# FPGA_POWER.net
KiCad netlist of a schematic drawn in Altium Designer
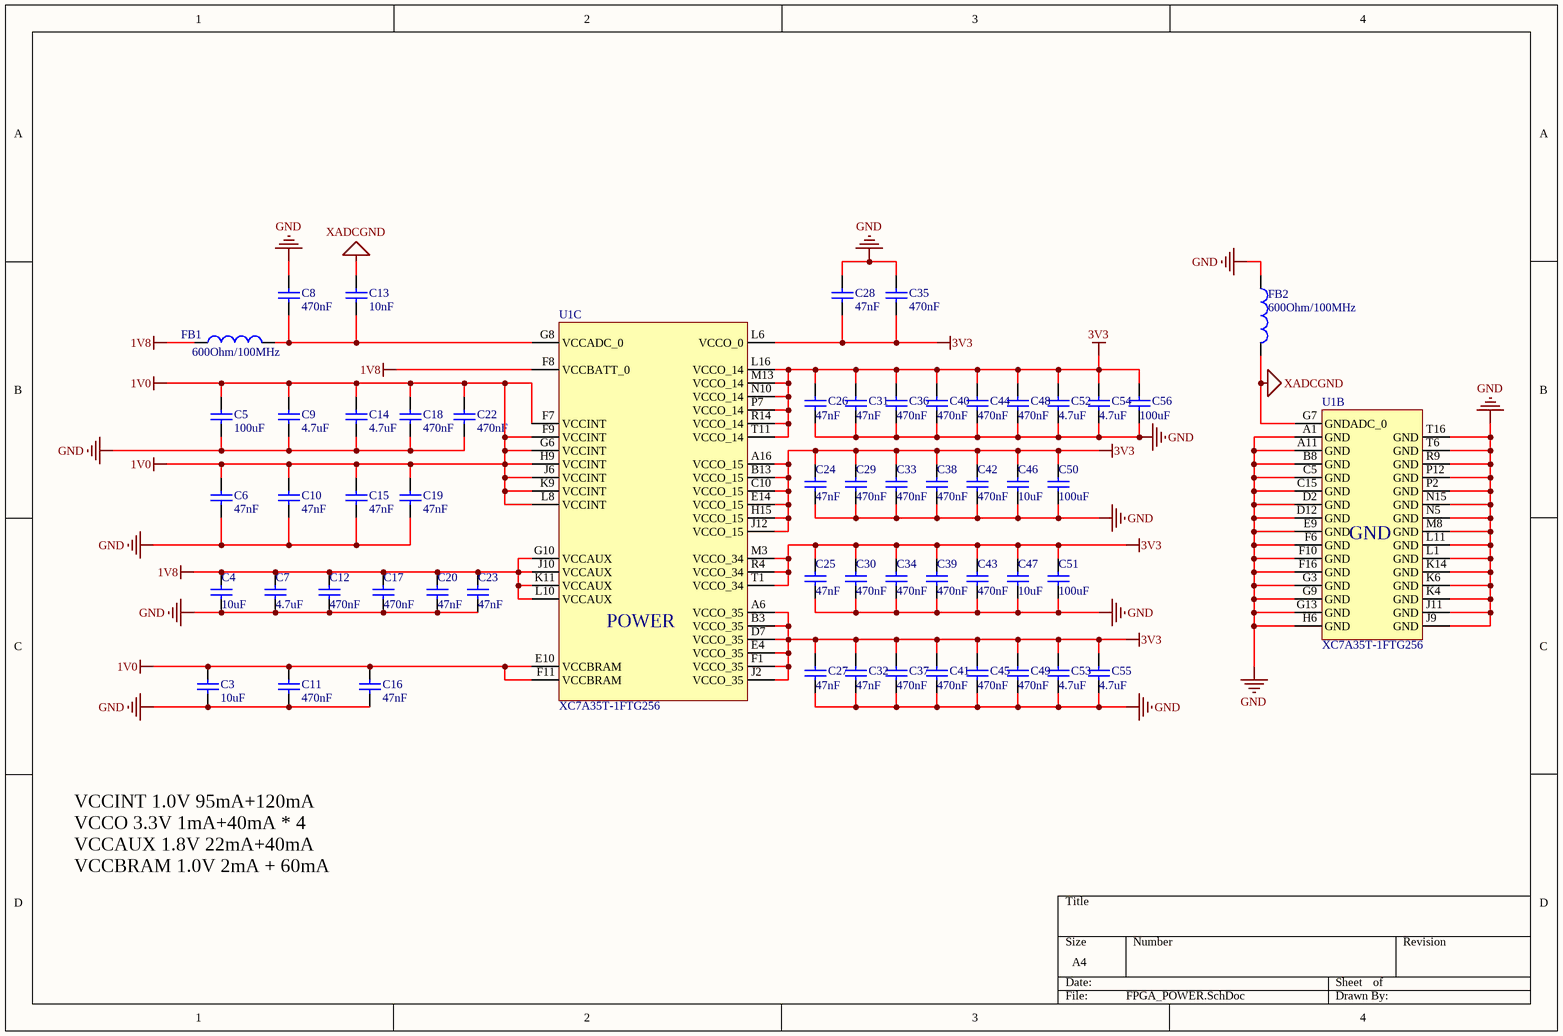
[diagram p0: FPGA_POWER.SchDoc]

(export (version "E")
  (design (tool "Eeschema 10.0.6"))
  (components
    (comp (ref "C3")
      (value "10uF")
      (footprint "0402")
      (description "贴片电容")
      (fields (field (name "Comment") "Cap") (field (name "PUBLISHER") "Altium Limited"))
      (libsource (lib "Sparks") (part "Cap"))
    )
    (comp (ref "C4")
      (value "10uF")
      (footprint "0402")
      (description "贴片电容")
      (fields (field (name "Comment") "Cap") (field (name "PUBLISHER") "Altium Limited"))
      (libsource (lib "Sparks") (part "Cap"))
    )
    (comp (ref "C5")
      (value "100uF")
      (footprint "2512")
      (description "贴片电容")
      (fields (field (name "Comment") "Cap") (field (name "PUBLISHER") "Altium Limited"))
      (libsource (lib "Sparks") (part "Cap"))
    )
    (comp (ref "C6")
      (value "47nF")
      (footprint "0402")
      (description "贴片电容")
      (fields (field (name "Comment") "Cap") (field (name "PUBLISHER") "Altium Limited"))
      (libsource (lib "Sparks") (part "Cap"))
    )
    (comp (ref "C7")
      (value "4.7uF")
      (footprint "0402")
      (description "贴片电容")
      (fields (field (name "Comment") "Cap") (field (name "PUBLISHER") "Altium Limited"))
      (libsource (lib "Sparks") (part "Cap"))
    )
    (comp (ref "C8")
      (value "470nF")
      (footprint "0402")
      (description "贴片电容")
      (fields (field (name "Comment") "Cap") (field (name "PUBLISHER") "Altium Limited"))
      (libsource (lib "Sparks") (part "Cap"))
    )
    (comp (ref "C9")
      (value "4.7uF")
      (footprint "0402")
      (description "贴片电容")
      (fields (field (name "Comment") "Cap") (field (name "PUBLISHER") "Altium Limited"))
      (libsource (lib "Sparks") (part "Cap"))
    )
    (comp (ref "C10")
      (value "47nF")
      (footprint "0402")
      (description "贴片电容")
      (fields (field (name "Comment") "Cap") (field (name "PUBLISHER") "Altium Limited"))
      (libsource (lib "Sparks") (part "Cap"))
    )
    (comp (ref "C11")
      (value "470nF")
      (footprint "0402")
      (description "贴片电容")
      (fields (field (name "Comment") "Cap") (field (name "PUBLISHER") "Altium Limited"))
      (libsource (lib "Sparks") (part "Cap"))
    )
    (comp (ref "C12")
      (value "470nF")
      (footprint "0402")
      (description "贴片电容")
      (fields (field (name "Comment") "Cap") (field (name "PUBLISHER") "Altium Limited"))
      (libsource (lib "Sparks") (part "Cap"))
    )
    (comp (ref "C13")
      (value "10nF")
      (footprint "0402")
      (description "贴片电容")
      (fields (field (name "Comment") "Cap") (field (name "PUBLISHER") "Altium Limited"))
      (libsource (lib "Sparks") (part "Cap"))
    )
    (comp (ref "C14")
      (value "4.7uF")
      (footprint "0402")
      (description "贴片电容")
      (fields (field (name "Comment") "Cap") (field (name "PUBLISHER") "Altium Limited"))
      (libsource (lib "Sparks") (part "Cap"))
    )
    (comp (ref "C15")
      (value "47nF")
      (footprint "0402")
      (description "贴片电容")
      (fields (field (name "Comment") "Cap") (field (name "PUBLISHER") "Altium Limited"))
      (libsource (lib "Sparks") (part "Cap"))
    )
    (comp (ref "C16")
      (value "47nF")
      (footprint "0402")
      (description "贴片电容")
      (fields (field (name "Comment") "Cap") (field (name "PUBLISHER") "Altium Limited"))
      (libsource (lib "Sparks") (part "Cap"))
    )
    (comp (ref "C17")
      (value "470nF")
      (footprint "0402")
      (description "贴片电容")
      (fields (field (name "Comment") "Cap") (field (name "PUBLISHER") "Altium Limited"))
      (libsource (lib "Sparks") (part "Cap"))
    )
    (comp (ref "C18")
      (value "470nF")
      (footprint "0402")
      (description "贴片电容")
      (fields (field (name "Comment") "Cap") (field (name "PUBLISHER") "Altium Limited"))
      (libsource (lib "Sparks") (part "Cap"))
    )
    (comp (ref "C19")
      (value "47nF")
      (footprint "0402")
      (description "贴片电容")
      (fields (field (name "Comment") "Cap") (field (name "PUBLISHER") "Altium Limited"))
      (libsource (lib "Sparks") (part "Cap"))
    )
    (comp (ref "C20")
      (value "47nF")
      (footprint "0402")
      (description "贴片电容")
      (fields (field (name "Comment") "Cap") (field (name "PUBLISHER") "Altium Limited"))
      (libsource (lib "Sparks") (part "Cap"))
    )
    (comp (ref "C22")
      (value "470nF")
      (footprint "0402")
      (description "贴片电容")
      (fields (field (name "Comment") "Cap") (field (name "PUBLISHER") "Altium Limited"))
      (libsource (lib "Sparks") (part "Cap"))
    )
    (comp (ref "C23")
      (value "47nF")
      (footprint "0402")
      (description "贴片电容")
      (fields (field (name "Comment") "Cap") (field (name "PUBLISHER") "Altium Limited"))
      (libsource (lib "Sparks") (part "Cap"))
    )
    (comp (ref "C24")
      (value "47nF")
      (footprint "0402")
      (description "贴片电容")
      (fields (field (name "Comment") "Cap") (field (name "PUBLISHER") "Altium Limited"))
      (libsource (lib "Sparks") (part "Cap"))
    )
    (comp (ref "C25")
      (value "47nF")
      (footprint "0402")
      (description "贴片电容")
      (fields (field (name "Comment") "Cap") (field (name "PUBLISHER") "Altium Limited"))
      (libsource (lib "Sparks") (part "Cap"))
    )
    (comp (ref "C26")
      (value "47nF")
      (footprint "0402")
      (description "贴片电容")
      (fields (field (name "Comment") "Cap") (field (name "PUBLISHER") "Altium Limited"))
      (libsource (lib "Sparks") (part "Cap"))
    )
    (comp (ref "C27")
      (value "47nF")
      (footprint "0402")
      (description "贴片电容")
      (fields (field (name "Comment") "Cap") (field (name "PUBLISHER") "Altium Limited"))
      (libsource (lib "Sparks") (part "Cap"))
    )
    (comp (ref "C28")
      (value "47nF")
      (footprint "0402")
      (description "贴片电容")
      (fields (field (name "Comment") "Cap") (field (name "PUBLISHER") "Altium Limited"))
      (libsource (lib "Sparks") (part "Cap"))
    )
    (comp (ref "C29")
      (value "470nF")
      (footprint "0402")
      (description "贴片电容")
      (fields (field (name "Comment") "Cap") (field (name "PUBLISHER") "Altium Limited"))
      (libsource (lib "Sparks") (part "Cap"))
    )
    (comp (ref "C30")
      (value "470nF")
      (footprint "0402")
      (description "贴片电容")
      (fields (field (name "Comment") "Cap") (field (name "PUBLISHER") "Altium Limited"))
      (libsource (lib "Sparks") (part "Cap"))
    )
    (comp (ref "C31")
      (value "47nF")
      (footprint "0402")
      (description "贴片电容")
      (fields (field (name "Comment") "Cap") (field (name "PUBLISHER") "Altium Limited"))
      (libsource (lib "Sparks") (part "Cap"))
    )
    (comp (ref "C32")
      (value "47nF")
      (footprint "0402")
      (description "贴片电容")
      (fields (field (name "Comment") "Cap") (field (name "PUBLISHER") "Altium Limited"))
      (libsource (lib "Sparks") (part "Cap"))
    )
    (comp (ref "C33")
      (value "470nF")
      (footprint "0402")
      (description "贴片电容")
      (fields (field (name "Comment") "Cap") (field (name "PUBLISHER") "Altium Limited"))
      (libsource (lib "Sparks") (part "Cap"))
    )
    (comp (ref "C34")
      (value "470nF")
      (footprint "0402")
      (description "贴片电容")
      (fields (field (name "Comment") "Cap") (field (name "PUBLISHER") "Altium Limited"))
      (libsource (lib "Sparks") (part "Cap"))
    )
    (comp (ref "C35")
      (value "470nF")
      (footprint "0402")
      (description "贴片电容")
      (fields (field (name "Comment") "Cap") (field (name "PUBLISHER") "Altium Limited"))
      (libsource (lib "Sparks") (part "Cap"))
    )
    (comp (ref "C36")
      (value "470nF")
      (footprint "0402")
      (description "贴片电容")
      (fields (field (name "Comment") "Cap") (field (name "PUBLISHER") "Altium Limited"))
      (libsource (lib "Sparks") (part "Cap"))
    )
    (comp (ref "C37")
      (value "470nF")
      (footprint "0402")
      (description "贴片电容")
      (fields (field (name "Comment") "Cap") (field (name "PUBLISHER") "Altium Limited"))
      (libsource (lib "Sparks") (part "Cap"))
    )
    (comp (ref "C38")
      (value "470nF")
      (footprint "0402")
      (description "贴片电容")
      (fields (field (name "Comment") "Cap") (field (name "PUBLISHER") "Altium Limited"))
      (libsource (lib "Sparks") (part "Cap"))
    )
    (comp (ref "C39")
      (value "470nF")
      (footprint "0402")
      (description "贴片电容")
      (fields (field (name "Comment") "Cap") (field (name "PUBLISHER") "Altium Limited"))
      (libsource (lib "Sparks") (part "Cap"))
    )
    (comp (ref "C40")
      (value "470nF")
      (footprint "0402")
      (description "贴片电容")
      (fields (field (name "Comment") "Cap") (field (name "PUBLISHER") "Altium Limited"))
      (libsource (lib "Sparks") (part "Cap"))
    )
    (comp (ref "C41")
      (value "470nF")
      (footprint "0402")
      (description "贴片电容")
      (fields (field (name "Comment") "Cap") (field (name "PUBLISHER") "Altium Limited"))
      (libsource (lib "Sparks") (part "Cap"))
    )
    (comp (ref "C42")
      (value "470nF")
      (footprint "0402")
      (description "贴片电容")
      (fields (field (name "Comment") "Cap") (field (name "PUBLISHER") "Altium Limited"))
      (libsource (lib "Sparks") (part "Cap"))
    )
    (comp (ref "C43")
      (value "470nF")
      (footprint "0402")
      (description "贴片电容")
      (fields (field (name "Comment") "Cap") (field (name "PUBLISHER") "Altium Limited"))
      (libsource (lib "Sparks") (part "Cap"))
    )
    (comp (ref "C44")
      (value "470nF")
      (footprint "0402")
      (description "贴片电容")
      (fields (field (name "Comment") "Cap") (field (name "PUBLISHER") "Altium Limited"))
      (libsource (lib "Sparks") (part "Cap"))
    )
    (comp (ref "C45")
      (value "470nF")
      (footprint "0402")
      (description "贴片电容")
      (fields (field (name "Comment") "Cap") (field (name "PUBLISHER") "Altium Limited"))
      (libsource (lib "Sparks") (part "Cap"))
    )
    (comp (ref "C46")
      (value "10uF")
      (footprint "0402")
      (description "贴片电容")
      (fields (field (name "Comment") "Cap") (field (name "PUBLISHER") "Altium Limited"))
      (libsource (lib "Sparks") (part "Cap"))
    )
    (comp (ref "C47")
      (value "10uF")
      (footprint "0402")
      (description "贴片电容")
      (fields (field (name "Comment") "Cap") (field (name "PUBLISHER") "Altium Limited"))
      (libsource (lib "Sparks") (part "Cap"))
    )
    (comp (ref "C48")
      (value "470nF")
      (footprint "0402")
      (description "贴片电容")
      (fields (field (name "Comment") "Cap") (field (name "PUBLISHER") "Altium Limited"))
      (libsource (lib "Sparks") (part "Cap"))
    )
    (comp (ref "C49")
      (value "470nF")
      (footprint "0402")
      (description "贴片电容")
      (fields (field (name "Comment") "Cap") (field (name "PUBLISHER") "Altium Limited"))
      (libsource (lib "Sparks") (part "Cap"))
    )
    (comp (ref "C50")
      (value "100uF")
      (footprint "2512")
      (description "贴片电容")
      (fields (field (name "Comment") "Cap") (field (name "PUBLISHER") "Altium Limited"))
      (libsource (lib "Sparks") (part "Cap"))
    )
    (comp (ref "C51")
      (value "100uF")
      (footprint "2512")
      (description "贴片电容")
      (fields (field (name "Comment") "Cap") (field (name "PUBLISHER") "Altium Limited"))
      (libsource (lib "Sparks") (part "Cap"))
    )
    (comp (ref "C52")
      (value "4.7uF")
      (footprint "0402")
      (description "贴片电容")
      (fields (field (name "Comment") "Cap") (field (name "PUBLISHER") "Altium Limited"))
      (libsource (lib "Sparks") (part "Cap"))
    )
    (comp (ref "C53")
      (value "4.7uF")
      (footprint "0402")
      (description "贴片电容")
      (fields (field (name "Comment") "Cap") (field (name "PUBLISHER") "Altium Limited"))
      (libsource (lib "Sparks") (part "Cap"))
    )
    (comp (ref "C54")
      (value "4.7uF")
      (footprint "0402")
      (description "贴片电容")
      (fields (field (name "Comment") "Cap") (field (name "PUBLISHER") "Altium Limited"))
      (libsource (lib "Sparks") (part "Cap"))
    )
    (comp (ref "C55")
      (value "4.7uF")
      (footprint "0402")
      (description "贴片电容")
      (fields (field (name "Comment") "Cap") (field (name "PUBLISHER") "Altium Limited"))
      (libsource (lib "Sparks") (part "Cap"))
    )
    (comp (ref "C56")
      (value "100uF")
      (footprint "2512")
      (description "贴片电容")
      (fields (field (name "Comment") "Cap") (field (name "PUBLISHER") "Altium Limited"))
      (libsource (lib "Sparks") (part "Cap"))
    )
    (comp (ref "FB1")
      (value "600Ohm/100MHz")
      (footprint "0402")
      (description "Inductor")
      (fields (field (name "PUBLISHER") "Altium Limited"))
      (libsource (lib "Miscellaneous Devices") (part "Inductor"))
    )
    (comp (ref "FB2")
      (value "600Ohm/100MHz")
      (footprint "0402")
      (description "Inductor")
      (fields (field (name "PUBLISHER") "Altium Limited"))
      (libsource (lib "Miscellaneous Devices") (part "Inductor"))
    )
    (comp (ref "U1")
      (value "XC7A35T-1FTG256")
      (footprint "BGA100P9X9-81A")
      (libsource (lib "Schlib") (part "XC7A35T-1FTG256"))
    )
  )
  (nets
    (net (code "1") (name "1V0") (class "Default")
      (node (ref "C10") (pin "1") (pinfunction "1_1") (pintype "passive"))
      (node (ref "C11") (pin "1") (pinfunction "1_1") (pintype "passive"))
      (node (ref "C14") (pin "1") (pinfunction "1_1") (pintype "passive"))
      (node (ref "C15") (pin "1") (pinfunction "1_1") (pintype "passive"))
      (node (ref "C16") (pin "1") (pinfunction "1_1") (pintype "passive"))
      (node (ref "C18") (pin "1") (pinfunction "1_1") (pintype "passive"))
      (node (ref "C19") (pin "1") (pinfunction "1_1") (pintype "passive"))
      (node (ref "C22") (pin "1") (pinfunction "1_1") (pintype "passive"))
      (node (ref "C3") (pin "1") (pinfunction "1_1") (pintype "passive"))
      (node (ref "C5") (pin "1") (pinfunction "1_1") (pintype "passive"))
      (node (ref "C6") (pin "1") (pinfunction "1_1") (pintype "passive"))
      (node (ref "C9") (pin "1") (pinfunction "1_1") (pintype "passive"))
      (node (ref "U1") (pin "E10") (pinfunction "VCCBRAM_E10") (pintype "passive"))
      (node (ref "U1") (pin "F11") (pinfunction "VCCBRAM_F11") (pintype "passive"))
      (node (ref "U1") (pin "F7") (pinfunction "VCCINT_F7") (pintype "passive"))
      (node (ref "U1") (pin "F9") (pinfunction "VCCINT_F9") (pintype "passive"))
      (node (ref "U1") (pin "G6") (pinfunction "VCCINT_G6") (pintype "passive"))
      (node (ref "U1") (pin "H9") (pinfunction "VCCINT_H9") (pintype "passive"))
      (node (ref "U1") (pin "J6") (pinfunction "VCCINT_J6") (pintype "passive"))
      (node (ref "U1") (pin "K9") (pinfunction "VCCINT_K9") (pintype "passive"))
      (node (ref "U1") (pin "L8") (pinfunction "VCCINT_L8") (pintype "passive"))
    )
    (net (code "2") (name "1V8") (class "Default")
      (node (ref "C12") (pin "1") (pinfunction "1_1") (pintype "passive"))
      (node (ref "C17") (pin "1") (pinfunction "1_1") (pintype "passive"))
      (node (ref "C20") (pin "1") (pinfunction "1_1") (pintype "passive"))
      (node (ref "C23") (pin "1") (pinfunction "1_1") (pintype "passive"))
      (node (ref "C4") (pin "1") (pinfunction "1_1") (pintype "passive"))
      (node (ref "C7") (pin "1") (pinfunction "1_1") (pintype "passive"))
      (node (ref "FB1") (pin "1") (pinfunction "1_1") (pintype "passive"))
      (node (ref "U1") (pin "F8") (pinfunction "VCCBATT_0_F8") (pintype "passive"))
      (node (ref "U1") (pin "G10") (pinfunction "VCCAUX_G10") (pintype "passive"))
      (node (ref "U1") (pin "J10") (pinfunction "VCCAUX_J10") (pintype "passive"))
      (node (ref "U1") (pin "K11") (pinfunction "VCCAUX_K11") (pintype "passive"))
      (node (ref "U1") (pin "L10") (pinfunction "VCCAUX_L10") (pintype "passive"))
    )
    (net (code "3") (name "3V3") (class "Default")
      (node (ref "C24") (pin "1") (pinfunction "1_1") (pintype "passive"))
      (node (ref "C25") (pin "1") (pinfunction "1_1") (pintype "passive"))
      (node (ref "C26") (pin "1") (pinfunction "1_1") (pintype "passive"))
      (node (ref "C27") (pin "1") (pinfunction "1_1") (pintype "passive"))
      (node (ref "C28") (pin "2") (pinfunction "2_2") (pintype "passive"))
      (node (ref "C29") (pin "1") (pinfunction "1_1") (pintype "passive"))
      (node (ref "C30") (pin "1") (pinfunction "1_1") (pintype "passive"))
      (node (ref "C31") (pin "1") (pinfunction "1_1") (pintype "passive"))
      (node (ref "C32") (pin "1") (pinfunction "1_1") (pintype "passive"))
      (node (ref "C33") (pin "1") (pinfunction "1_1") (pintype "passive"))
      (node (ref "C34") (pin "1") (pinfunction "1_1") (pintype "passive"))
      (node (ref "C35") (pin "2") (pinfunction "2_2") (pintype "passive"))
      (node (ref "C36") (pin "1") (pinfunction "1_1") (pintype "passive"))
      (node (ref "C37") (pin "1") (pinfunction "1_1") (pintype "passive"))
      (node (ref "C38") (pin "1") (pinfunction "1_1") (pintype "passive"))
      (node (ref "C39") (pin "1") (pinfunction "1_1") (pintype "passive"))
      (node (ref "C40") (pin "1") (pinfunction "1_1") (pintype "passive"))
      (node (ref "C41") (pin "1") (pinfunction "1_1") (pintype "passive"))
      (node (ref "C42") (pin "1") (pinfunction "1_1") (pintype "passive"))
      (node (ref "C43") (pin "1") (pinfunction "1_1") (pintype "passive"))
      (node (ref "C44") (pin "1") (pinfunction "1_1") (pintype "passive"))
      (node (ref "C45") (pin "1") (pinfunction "1_1") (pintype "passive"))
      (node (ref "C46") (pin "1") (pinfunction "1_1") (pintype "passive"))
      (node (ref "C47") (pin "1") (pinfunction "1_1") (pintype "passive"))
      (node (ref "C48") (pin "1") (pinfunction "1_1") (pintype "passive"))
      (node (ref "C49") (pin "1") (pinfunction "1_1") (pintype "passive"))
      (node (ref "C50") (pin "1") (pinfunction "1_1") (pintype "passive"))
      (node (ref "C51") (pin "1") (pinfunction "1_1") (pintype "passive"))
      (node (ref "C52") (pin "1") (pinfunction "1_1") (pintype "passive"))
      (node (ref "C53") (pin "1") (pinfunction "1_1") (pintype "passive"))
      (node (ref "C54") (pin "1") (pinfunction "1_1") (pintype "passive"))
      (node (ref "C55") (pin "1") (pinfunction "1_1") (pintype "passive"))
      (node (ref "C56") (pin "1") (pinfunction "1_1") (pintype "passive"))
      (node (ref "U1") (pin "A16") (pinfunction "VCCO_15_A16") (pintype "passive"))
      (node (ref "U1") (pin "A6") (pinfunction "VCCO_35_A6") (pintype "passive"))
      (node (ref "U1") (pin "B13") (pinfunction "VCCO_15_B13") (pintype "passive"))
      (node (ref "U1") (pin "B3") (pinfunction "VCCO_35_B3") (pintype "passive"))
      (node (ref "U1") (pin "C10") (pinfunction "VCCO_15_C10") (pintype "passive"))
      (node (ref "U1") (pin "D7") (pinfunction "VCCO_35_D7") (pintype "passive"))
      (node (ref "U1") (pin "E14") (pinfunction "VCCO_15_E14") (pintype "passive"))
      (node (ref "U1") (pin "E4") (pinfunction "VCCO_35_E4") (pintype "passive"))
      (node (ref "U1") (pin "F1") (pinfunction "VCCO_35_F1") (pintype "passive"))
      (node (ref "U1") (pin "H15") (pinfunction "VCCO_15_H15") (pintype "passive"))
      (node (ref "U1") (pin "J12") (pinfunction "VCCO_15_J12") (pintype "passive"))
      (node (ref "U1") (pin "J2") (pinfunction "VCCO_35_J2") (pintype "passive"))
      (node (ref "U1") (pin "L16") (pinfunction "VCCO_14_L16") (pintype "passive"))
      (node (ref "U1") (pin "L6") (pinfunction "VCCO_0_L6") (pintype "passive"))
      (node (ref "U1") (pin "M13") (pinfunction "VCCO_14_M13") (pintype "passive"))
      (node (ref "U1") (pin "M3") (pinfunction "VCCO_34_M3") (pintype "passive"))
      (node (ref "U1") (pin "N10") (pinfunction "VCCO_14_N10") (pintype "passive"))
      (node (ref "U1") (pin "P7") (pinfunction "VCCO_14_P7") (pintype "passive"))
      (node (ref "U1") (pin "R14") (pinfunction "VCCO_14_R14") (pintype "passive"))
      (node (ref "U1") (pin "R4") (pinfunction "VCCO_34_R4") (pintype "passive"))
      (node (ref "U1") (pin "T1") (pinfunction "VCCO_34_T1") (pintype "passive"))
      (node (ref "U1") (pin "T11") (pinfunction "VCCO_14_T11") (pintype "passive"))
    )
    (net (code "4") (name "GND") (class "Default")
      (node (ref "C10") (pin "2") (pinfunction "2_2") (pintype "passive"))
      (node (ref "C11") (pin "2") (pinfunction "2_2") (pintype "passive"))
      (node (ref "C12") (pin "2") (pinfunction "2_2") (pintype "passive"))
      (node (ref "C14") (pin "2") (pinfunction "2_2") (pintype "passive"))
      (node (ref "C15") (pin "2") (pinfunction "2_2") (pintype "passive"))
      (node (ref "C16") (pin "2") (pinfunction "2_2") (pintype "passive"))
      (node (ref "C17") (pin "2") (pinfunction "2_2") (pintype "passive"))
      (node (ref "C18") (pin "2") (pinfunction "2_2") (pintype "passive"))
      (node (ref "C19") (pin "2") (pinfunction "2_2") (pintype "passive"))
      (node (ref "C20") (pin "2") (pinfunction "2_2") (pintype "passive"))
      (node (ref "C22") (pin "2") (pinfunction "2_2") (pintype "passive"))
      (node (ref "C23") (pin "2") (pinfunction "2_2") (pintype "passive"))
      (node (ref "C24") (pin "2") (pinfunction "2_2") (pintype "passive"))
      (node (ref "C25") (pin "2") (pinfunction "2_2") (pintype "passive"))
      (node (ref "C26") (pin "2") (pinfunction "2_2") (pintype "passive"))
      (node (ref "C27") (pin "2") (pinfunction "2_2") (pintype "passive"))
      (node (ref "C28") (pin "1") (pinfunction "1_1") (pintype "passive"))
      (node (ref "C29") (pin "2") (pinfunction "2_2") (pintype "passive"))
      (node (ref "C3") (pin "2") (pinfunction "2_2") (pintype "passive"))
      (node (ref "C30") (pin "2") (pinfunction "2_2") (pintype "passive"))
      (node (ref "C31") (pin "2") (pinfunction "2_2") (pintype "passive"))
      (node (ref "C32") (pin "2") (pinfunction "2_2") (pintype "passive"))
      (node (ref "C33") (pin "2") (pinfunction "2_2") (pintype "passive"))
      (node (ref "C34") (pin "2") (pinfunction "2_2") (pintype "passive"))
      (node (ref "C35") (pin "1") (pinfunction "1_1") (pintype "passive"))
      (node (ref "C36") (pin "2") (pinfunction "2_2") (pintype "passive"))
      (node (ref "C37") (pin "2") (pinfunction "2_2") (pintype "passive"))
      (node (ref "C38") (pin "2") (pinfunction "2_2") (pintype "passive"))
      (node (ref "C39") (pin "2") (pinfunction "2_2") (pintype "passive"))
      (node (ref "C4") (pin "2") (pinfunction "2_2") (pintype "passive"))
      (node (ref "C40") (pin "2") (pinfunction "2_2") (pintype "passive"))
      (node (ref "C41") (pin "2") (pinfunction "2_2") (pintype "passive"))
      (node (ref "C42") (pin "2") (pinfunction "2_2") (pintype "passive"))
      (node (ref "C43") (pin "2") (pinfunction "2_2") (pintype "passive"))
      (node (ref "C44") (pin "2") (pinfunction "2_2") (pintype "passive"))
      (node (ref "C45") (pin "2") (pinfunction "2_2") (pintype "passive"))
      (node (ref "C46") (pin "2") (pinfunction "2_2") (pintype "passive"))
      (node (ref "C47") (pin "2") (pinfunction "2_2") (pintype "passive"))
      (node (ref "C48") (pin "2") (pinfunction "2_2") (pintype "passive"))
      (node (ref "C49") (pin "2") (pinfunction "2_2") (pintype "passive"))
      (node (ref "C5") (pin "2") (pinfunction "2_2") (pintype "passive"))
      (node (ref "C50") (pin "2") (pinfunction "2_2") (pintype "passive"))
      (node (ref "C51") (pin "2") (pinfunction "2_2") (pintype "passive"))
      (node (ref "C52") (pin "2") (pinfunction "2_2") (pintype "passive"))
      (node (ref "C53") (pin "2") (pinfunction "2_2") (pintype "passive"))
      (node (ref "C54") (pin "2") (pinfunction "2_2") (pintype "passive"))
      (node (ref "C55") (pin "2") (pinfunction "2_2") (pintype "passive"))
      (node (ref "C56") (pin "2") (pinfunction "2_2") (pintype "passive"))
      (node (ref "C6") (pin "2") (pinfunction "2_2") (pintype "passive"))
      (node (ref "C7") (pin "2") (pinfunction "2_2") (pintype "passive"))
      (node (ref "C8") (pin "1") (pinfunction "1_1") (pintype "passive"))
      (node (ref "C9") (pin "2") (pinfunction "2_2") (pintype "passive"))
      (node (ref "FB2") (pin "1") (pinfunction "1_1") (pintype "passive"))
      (node (ref "U1") (pin "A1") (pinfunction "GND_A1") (pintype "passive"))
      (node (ref "U1") (pin "A11") (pinfunction "GND_A11") (pintype "passive"))
      (node (ref "U1") (pin "B8") (pinfunction "GND_B8") (pintype "passive"))
      (node (ref "U1") (pin "C15") (pinfunction "GND_C15") (pintype "passive"))
      (node (ref "U1") (pin "C5") (pinfunction "GND_C5") (pintype "passive"))
      (node (ref "U1") (pin "D12") (pinfunction "GND_D12") (pintype "passive"))
      (node (ref "U1") (pin "D2") (pinfunction "GND_D2") (pintype "passive"))
      (node (ref "U1") (pin "E9") (pinfunction "GND_E9") (pintype "passive"))
      (node (ref "U1") (pin "F10") (pinfunction "GND_F10") (pintype "passive"))
      (node (ref "U1") (pin "F16") (pinfunction "GND_F16") (pintype "passive"))
      (node (ref "U1") (pin "F6") (pinfunction "GND_F6") (pintype "passive"))
      (node (ref "U1") (pin "G13") (pinfunction "GND_G13") (pintype "passive"))
      (node (ref "U1") (pin "G3") (pinfunction "GND_G3") (pintype "passive"))
      (node (ref "U1") (pin "G9") (pinfunction "GND_G9") (pintype "passive"))
      (node (ref "U1") (pin "H6") (pinfunction "GND_H6") (pintype "passive"))
      (node (ref "U1") (pin "J11") (pinfunction "GND_J11") (pintype "passive"))
      (node (ref "U1") (pin "J9") (pinfunction "GND_J9") (pintype "passive"))
      (node (ref "U1") (pin "K14") (pinfunction "GND_K14") (pintype "passive"))
      (node (ref "U1") (pin "K4") (pinfunction "GND_K4") (pintype "passive"))
      (node (ref "U1") (pin "K6") (pinfunction "GND_K6") (pintype "passive"))
      (node (ref "U1") (pin "L1") (pinfunction "GND_L1") (pintype "passive"))
      (node (ref "U1") (pin "L11") (pinfunction "GND_L11") (pintype "passive"))
      (node (ref "U1") (pin "M8") (pinfunction "GND_M8") (pintype "passive"))
      (node (ref "U1") (pin "N15") (pinfunction "GND_N15") (pintype "passive"))
      (node (ref "U1") (pin "N5") (pinfunction "GND_N5") (pintype "passive"))
      (node (ref "U1") (pin "P12") (pinfunction "GND_P12") (pintype "passive"))
      (node (ref "U1") (pin "P2") (pinfunction "GND_P2") (pintype "passive"))
      (node (ref "U1") (pin "R9") (pinfunction "GND_R9") (pintype "passive"))
      (node (ref "U1") (pin "T16") (pinfunction "GND_T16") (pintype "passive"))
      (node (ref "U1") (pin "T6") (pinfunction "GND_T6") (pintype "passive"))
    )
    (net (code "5") (name "Net-(U1C-VCCADC_0)") (class "Default")
      (node (ref "C13") (pin "1") (pinfunction "1_1") (pintype "passive"))
      (node (ref "C8") (pin "2") (pinfunction "2_2") (pintype "passive"))
      (node (ref "FB1") (pin "2") (pinfunction "2_2") (pintype "passive"))
      (node (ref "U1") (pin "G8") (pinfunction "VCCADC_0_G8") (pintype "passive"))
    )
    (net (code "6") (name "XADCGND") (class "Default")
      (node (ref "C13") (pin "2") (pinfunction "2_2") (pintype "passive"))
      (node (ref "FB2") (pin "2") (pinfunction "2_2") (pintype "passive"))
      (node (ref "U1") (pin "G7") (pinfunction "GNDADC_0_G7") (pintype "passive"))
    )
  )
)
